# untitled_3.net
KiCad netlist of a schematic drawn in EAGLE
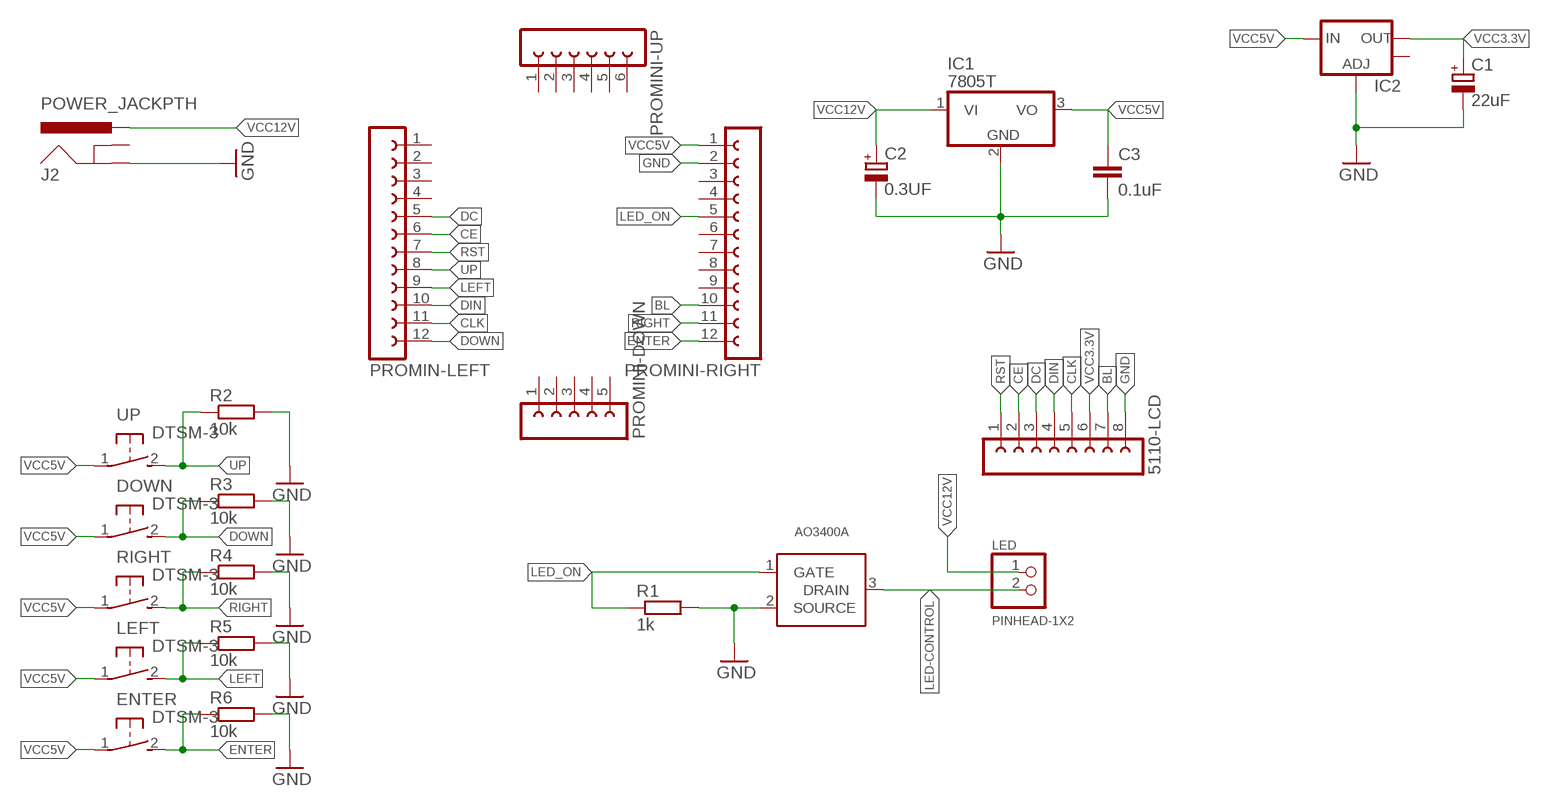
[diagram p0: schematic, sheet 1]

(export (version "E")
  (design (tool "Eeschema 10.0.6"))
  (components
    (comp (ref "5110-LCD")
      (value "FE08-1")
      (footprint "eagle-import:FE08")
      (libsource (lib "eagle-import") (part "FE08-1"))
    )
    (comp (ref "C1")
      (value "22uF")
      (footprint "eagle-import:E2-5")
      (libsource (lib "eagle-import") (part "CPOL-EUE2-5"))
    )
    (comp (ref "C2")
      (value "0.3UF")
      (footprint "eagle-import:E5-5")
      (libsource (lib "eagle-import") (part "CPOL-EUE5-5"))
    )
    (comp (ref "C3")
      (value "0.1uF")
      (footprint "eagle-import:C050-025X075")
      (libsource (lib "eagle-import") (part "C-EU050-025X075"))
    )
    (comp (ref "DOWN")
      (value "DTSM-3")
      (footprint "eagle-import:DTSM-3")
      (libsource (lib "eagle-import") (part "DTSM-3"))
    )
    (comp (ref "ENTER")
      (value "DTSM-3")
      (footprint "eagle-import:DTSM-3")
      (libsource (lib "eagle-import") (part "DTSM-3"))
    )
    (comp (ref "IC1")
      (value "7805T")
      (footprint "eagle-import:TO220H")
      (libsource (lib "eagle-import") (part "78T05"))
    )
    (comp (ref "IC2")
      (value "V_REG_LM1117SOT223")
      (footprint "eagle-import:SOT223")
      (libsource (lib "eagle-import") (part "V_REG_LM1117SOT223"))
    )
    (comp (ref "J2")
      (value "POWER_JACKPTH")
      (footprint "eagle-import:POWER_JACK_PTH")
      (libsource (lib "eagle-import") (part "POWER_JACKPTH"))
    )
    (comp (ref "LED")
      (value "PINHEAD-1X2")
      (footprint "eagle-import:PIHEAD-1X2")
      (libsource (lib "eagle-import") (part "PINHEAD-1X2"))
    )
    (comp (ref "LEFT")
      (value "DTSM-3")
      (footprint "eagle-import:DTSM-3")
      (libsource (lib "eagle-import") (part "DTSM-3"))
    )
    (comp (ref "PROMIN-LEFT")
      (value "FE12-1")
      (footprint "eagle-import:FE12")
      (libsource (lib "eagle-import") (part "FE12-1"))
    )
    (comp (ref "PROMINI-DOWN")
      (value "FE05-1")
      (footprint "eagle-import:FE05-1")
      (libsource (lib "eagle-import") (part "FE05-1"))
    )
    (comp (ref "PROMINI-RIGHT")
      (value "FE12-1")
      (footprint "eagle-import:FE12")
      (libsource (lib "eagle-import") (part "FE12-1"))
    )
    (comp (ref "PROMINI-UP")
      (value "FE06-1")
      (footprint "eagle-import:FE06")
      (libsource (lib "eagle-import") (part "FE06-1"))
    )
    (comp (ref "R1")
      (value "1k")
      (footprint "eagle-import:R1206")
      (libsource (lib "eagle-import") (part "R-EU_R1206"))
    )
    (comp (ref "R2")
      (value "10k")
      (footprint "eagle-import:R1206")
      (libsource (lib "eagle-import") (part "R-EU_R1206"))
    )
    (comp (ref "R3")
      (value "10k")
      (footprint "eagle-import:R1206")
      (libsource (lib "eagle-import") (part "R-EU_R1206"))
    )
    (comp (ref "R4")
      (value "10k")
      (footprint "eagle-import:R1206")
      (libsource (lib "eagle-import") (part "R-EU_R1206"))
    )
    (comp (ref "R5")
      (value "10k")
      (footprint "eagle-import:R1206")
      (libsource (lib "eagle-import") (part "R-EU_R1206"))
    )
    (comp (ref "R6")
      (value "10k")
      (footprint "eagle-import:R1206")
      (libsource (lib "eagle-import") (part "R-EU_R1206"))
    )
    (comp (ref "RIGHT")
      (value "DTSM-3")
      (footprint "eagle-import:DTSM-3")
      (libsource (lib "eagle-import") (part "DTSM-3"))
    )
    (comp (ref "U$1")
      (value "AO3400A")
      (footprint "eagle-import:SOT-23")
      (libsource (lib "eagle-import") (part "AO3400A"))
    )
    (comp (ref "UP")
      (value "DTSM-3")
      (footprint "eagle-import:DTSM-3")
      (libsource (lib "eagle-import") (part "DTSM-3"))
    )
  )
  (nets
    (net (code "1") (name "BL") (class "Default")
      (node (ref "5110-LCD") (pin "7") (pinfunction "7_7") (pintype "passive"))
      (node (ref "PROMINI-RIGHT") (pin "10") (pinfunction "10_10") (pintype "passive"))
    )
    (net (code "2") (name "CE") (class "Default")
      (node (ref "5110-LCD") (pin "2") (pinfunction "2_2") (pintype "passive"))
      (node (ref "PROMIN-LEFT") (pin "6") (pinfunction "6_6") (pintype "passive"))
    )
    (net (code "3") (name "CLK") (class "Default")
      (node (ref "5110-LCD") (pin "5") (pinfunction "5_5") (pintype "passive"))
      (node (ref "PROMIN-LEFT") (pin "11") (pinfunction "11_11") (pintype "passive"))
    )
    (net (code "4") (name "DC") (class "Default")
      (node (ref "5110-LCD") (pin "3") (pinfunction "3_3") (pintype "passive"))
      (node (ref "PROMIN-LEFT") (pin "5") (pinfunction "5_5") (pintype "passive"))
    )
    (net (code "5") (name "DIN") (class "Default")
      (node (ref "5110-LCD") (pin "4") (pinfunction "4_4") (pintype "passive"))
      (node (ref "PROMIN-LEFT") (pin "10") (pinfunction "10_10") (pintype "passive"))
    )
    (net (code "6") (name "DOWN") (class "Default")
      (node (ref "DOWN") (pin "2") (pinfunction "2_2") (pintype "passive"))
      (node (ref "PROMIN-LEFT") (pin "12") (pinfunction "12_12") (pintype "passive"))
      (node (ref "R3") (pin "1") (pinfunction "1_1") (pintype "passive"))
    )
    (net (code "7") (name "ENTER") (class "Default")
      (node (ref "ENTER") (pin "2") (pinfunction "2_2") (pintype "passive"))
      (node (ref "PROMINI-RIGHT") (pin "12") (pinfunction "12_12") (pintype "passive"))
      (node (ref "R6") (pin "1") (pinfunction "1_1") (pintype "passive"))
    )
    (net (code "8") (name "GND") (class "Default")
      (node (ref "5110-LCD") (pin "8") (pinfunction "8_8") (pintype "passive"))
      (node (ref "C1") (pin "-") (pinfunction "-_-") (pintype "passive"))
      (node (ref "C2") (pin "-") (pinfunction "-_-") (pintype "passive"))
      (node (ref "C3") (pin "2") (pinfunction "2_2") (pintype "passive"))
      (node (ref "IC1") (pin "2") (pinfunction "GND_2") (pintype "passive"))
      (node (ref "IC2") (pin "1") (pinfunction "ADJ_1") (pintype "input"))
      (node (ref "J2") (pin "GND") (pinfunction "GND_GND") (pintype "bidirectional"))
      (node (ref "PROMINI-RIGHT") (pin "2") (pinfunction "2_2") (pintype "passive"))
      (node (ref "R1") (pin "2") (pinfunction "2_2") (pintype "passive"))
      (node (ref "R2") (pin "2") (pinfunction "2_2") (pintype "passive"))
      (node (ref "R3") (pin "2") (pinfunction "2_2") (pintype "passive"))
      (node (ref "R4") (pin "2") (pinfunction "2_2") (pintype "passive"))
      (node (ref "R5") (pin "2") (pinfunction "2_2") (pintype "passive"))
      (node (ref "R6") (pin "2") (pinfunction "2_2") (pintype "passive"))
      (node (ref "U$1") (pin "2") (pinfunction "SOURCE_2") (pintype "bidirectional"))
    )
    (net (code "9") (name "LED-CONTROL") (class "Default")
      (node (ref "LED") (pin "2") (pinfunction "2_2") (pintype "passive"))
      (node (ref "U$1") (pin "3") (pinfunction "DRAIN_3") (pintype "bidirectional"))
    )
    (net (code "10") (name "LED_ON") (class "Default")
      (node (ref "PROMINI-RIGHT") (pin "5") (pinfunction "5_5") (pintype "passive"))
      (node (ref "R1") (pin "1") (pinfunction "1_1") (pintype "passive"))
      (node (ref "U$1") (pin "1") (pinfunction "GATE_1") (pintype "bidirectional"))
    )
    (net (code "11") (name "LEFT") (class "Default")
      (node (ref "LEFT") (pin "2") (pinfunction "2_2") (pintype "passive"))
      (node (ref "PROMIN-LEFT") (pin "9") (pinfunction "9_9") (pintype "passive"))
      (node (ref "R5") (pin "1") (pinfunction "1_1") (pintype "passive"))
    )
    (net (code "12") (name "RIGHT") (class "Default")
      (node (ref "PROMINI-RIGHT") (pin "11") (pinfunction "11_11") (pintype "passive"))
      (node (ref "R4") (pin "1") (pinfunction "1_1") (pintype "passive"))
      (node (ref "RIGHT") (pin "2") (pinfunction "2_2") (pintype "passive"))
    )
    (net (code "13") (name "RST") (class "Default")
      (node (ref "5110-LCD") (pin "1") (pinfunction "1_1") (pintype "passive"))
      (node (ref "PROMIN-LEFT") (pin "7") (pinfunction "7_7") (pintype "passive"))
    )
    (net (code "14") (name "UP") (class "Default")
      (node (ref "PROMIN-LEFT") (pin "8") (pinfunction "8_8") (pintype "passive"))
      (node (ref "R2") (pin "1") (pinfunction "1_1") (pintype "passive"))
      (node (ref "UP") (pin "2") (pinfunction "2_2") (pintype "passive"))
    )
    (net (code "15") (name "VCC3.3V") (class "Default")
      (node (ref "5110-LCD") (pin "6") (pinfunction "6_6") (pintype "passive"))
      (node (ref "C1") (pin "+") (pinfunction "+_+") (pintype "passive"))
      (node (ref "IC2") (pin "2") (pinfunction "OUT_2") (pintype "output"))
    )
    (net (code "16") (name "VCC5V") (class "Default")
      (node (ref "C3") (pin "1") (pinfunction "1_1") (pintype "passive"))
      (node (ref "DOWN") (pin "1") (pinfunction "1_1") (pintype "passive"))
      (node (ref "ENTER") (pin "1") (pinfunction "1_1") (pintype "passive"))
      (node (ref "IC1") (pin "3") (pinfunction "VO_3") (pintype "passive"))
      (node (ref "IC2") (pin "3") (pinfunction "IN_3") (pintype "input"))
      (node (ref "LEFT") (pin "1") (pinfunction "1_1") (pintype "passive"))
      (node (ref "PROMINI-RIGHT") (pin "1") (pinfunction "1_1") (pintype "passive"))
      (node (ref "RIGHT") (pin "1") (pinfunction "1_1") (pintype "passive"))
      (node (ref "UP") (pin "1") (pinfunction "1_1") (pintype "passive"))
    )
    (net (code "17") (name "VCC12V") (class "Default")
      (node (ref "C2") (pin "+") (pinfunction "+_+") (pintype "passive"))
      (node (ref "IC1") (pin "1") (pinfunction "VI_1") (pintype "input"))
      (node (ref "J2") (pin "PWR") (pinfunction "PWR_PWR") (pintype "bidirectional"))
      (node (ref "LED") (pin "1") (pinfunction "1_1") (pintype "passive"))
    )
    (net (code "18") (name "unconnected-(IC2-OUT-Pad4)") (class "Default")
      (node (ref "IC2") (pin "4") (pinfunction "OUT_4") (pintype "output"))
    )
    (net (code "19") (name "unconnected-(J2-PadGNDBREAK)") (class "Default")
      (node (ref "J2") (pin "GNDBREAK") (pinfunction "GNDBREAK_GNDBREAK") (pintype "bidirectional"))
    )
    (net (code "20") (name "unconnected-(PROMIN-LEFT-Pad1)") (class "Default")
      (node (ref "PROMIN-LEFT") (pin "1") (pinfunction "1_1") (pintype "passive"))
    )
    (net (code "21") (name "unconnected-(PROMIN-LEFT-Pad2)") (class "Default")
      (node (ref "PROMIN-LEFT") (pin "2") (pinfunction "2_2") (pintype "passive"))
    )
    (net (code "22") (name "unconnected-(PROMIN-LEFT-Pad3)") (class "Default")
      (node (ref "PROMIN-LEFT") (pin "3") (pinfunction "3_3") (pintype "passive"))
    )
    (net (code "23") (name "unconnected-(PROMIN-LEFT-Pad4)") (class "Default")
      (node (ref "PROMIN-LEFT") (pin "4") (pinfunction "4_4") (pintype "passive"))
    )
    (net (code "24") (name "unconnected-(PROMINI-DOWN-Pad1)") (class "Default")
      (node (ref "PROMINI-DOWN") (pin "1") (pinfunction "1_1") (pintype "passive"))
    )
    (net (code "25") (name "unconnected-(PROMINI-DOWN-Pad2)") (class "Default")
      (node (ref "PROMINI-DOWN") (pin "2") (pinfunction "2_2") (pintype "passive"))
    )
    (net (code "26") (name "unconnected-(PROMINI-DOWN-Pad3)") (class "Default")
      (node (ref "PROMINI-DOWN") (pin "3") (pinfunction "3_3") (pintype "passive"))
    )
    (net (code "27") (name "unconnected-(PROMINI-DOWN-Pad4)") (class "Default")
      (node (ref "PROMINI-DOWN") (pin "4") (pinfunction "4_4") (pintype "passive"))
    )
    (net (code "28") (name "unconnected-(PROMINI-DOWN-Pad5)") (class "Default")
      (node (ref "PROMINI-DOWN") (pin "5") (pinfunction "5_5") (pintype "passive"))
    )
    (net (code "29") (name "unconnected-(PROMINI-RIGHT-Pad3)") (class "Default")
      (node (ref "PROMINI-RIGHT") (pin "3") (pinfunction "3_3") (pintype "passive"))
    )
    (net (code "30") (name "unconnected-(PROMINI-RIGHT-Pad4)") (class "Default")
      (node (ref "PROMINI-RIGHT") (pin "4") (pinfunction "4_4") (pintype "passive"))
    )
    (net (code "31") (name "unconnected-(PROMINI-RIGHT-Pad6)") (class "Default")
      (node (ref "PROMINI-RIGHT") (pin "6") (pinfunction "6_6") (pintype "passive"))
    )
    (net (code "32") (name "unconnected-(PROMINI-RIGHT-Pad7)") (class "Default")
      (node (ref "PROMINI-RIGHT") (pin "7") (pinfunction "7_7") (pintype "passive"))
    )
    (net (code "33") (name "unconnected-(PROMINI-RIGHT-Pad8)") (class "Default")
      (node (ref "PROMINI-RIGHT") (pin "8") (pinfunction "8_8") (pintype "passive"))
    )
    (net (code "34") (name "unconnected-(PROMINI-RIGHT-Pad9)") (class "Default")
      (node (ref "PROMINI-RIGHT") (pin "9") (pinfunction "9_9") (pintype "passive"))
    )
    (net (code "35") (name "unconnected-(PROMINI-UP-Pad1)") (class "Default")
      (node (ref "PROMINI-UP") (pin "1") (pinfunction "1_1") (pintype "passive"))
    )
    (net (code "36") (name "unconnected-(PROMINI-UP-Pad2)") (class "Default")
      (node (ref "PROMINI-UP") (pin "2") (pinfunction "2_2") (pintype "passive"))
    )
    (net (code "37") (name "unconnected-(PROMINI-UP-Pad3)") (class "Default")
      (node (ref "PROMINI-UP") (pin "3") (pinfunction "3_3") (pintype "passive"))
    )
    (net (code "38") (name "unconnected-(PROMINI-UP-Pad4)") (class "Default")
      (node (ref "PROMINI-UP") (pin "4") (pinfunction "4_4") (pintype "passive"))
    )
    (net (code "39") (name "unconnected-(PROMINI-UP-Pad5)") (class "Default")
      (node (ref "PROMINI-UP") (pin "5") (pinfunction "5_5") (pintype "passive"))
    )
    (net (code "40") (name "unconnected-(PROMINI-UP-Pad6)") (class "Default")
      (node (ref "PROMINI-UP") (pin "6") (pinfunction "6_6") (pintype "passive"))
    )
  )
)
